# Ethernet.net
KiCad netlist of a schematic drawn in Altium Designer
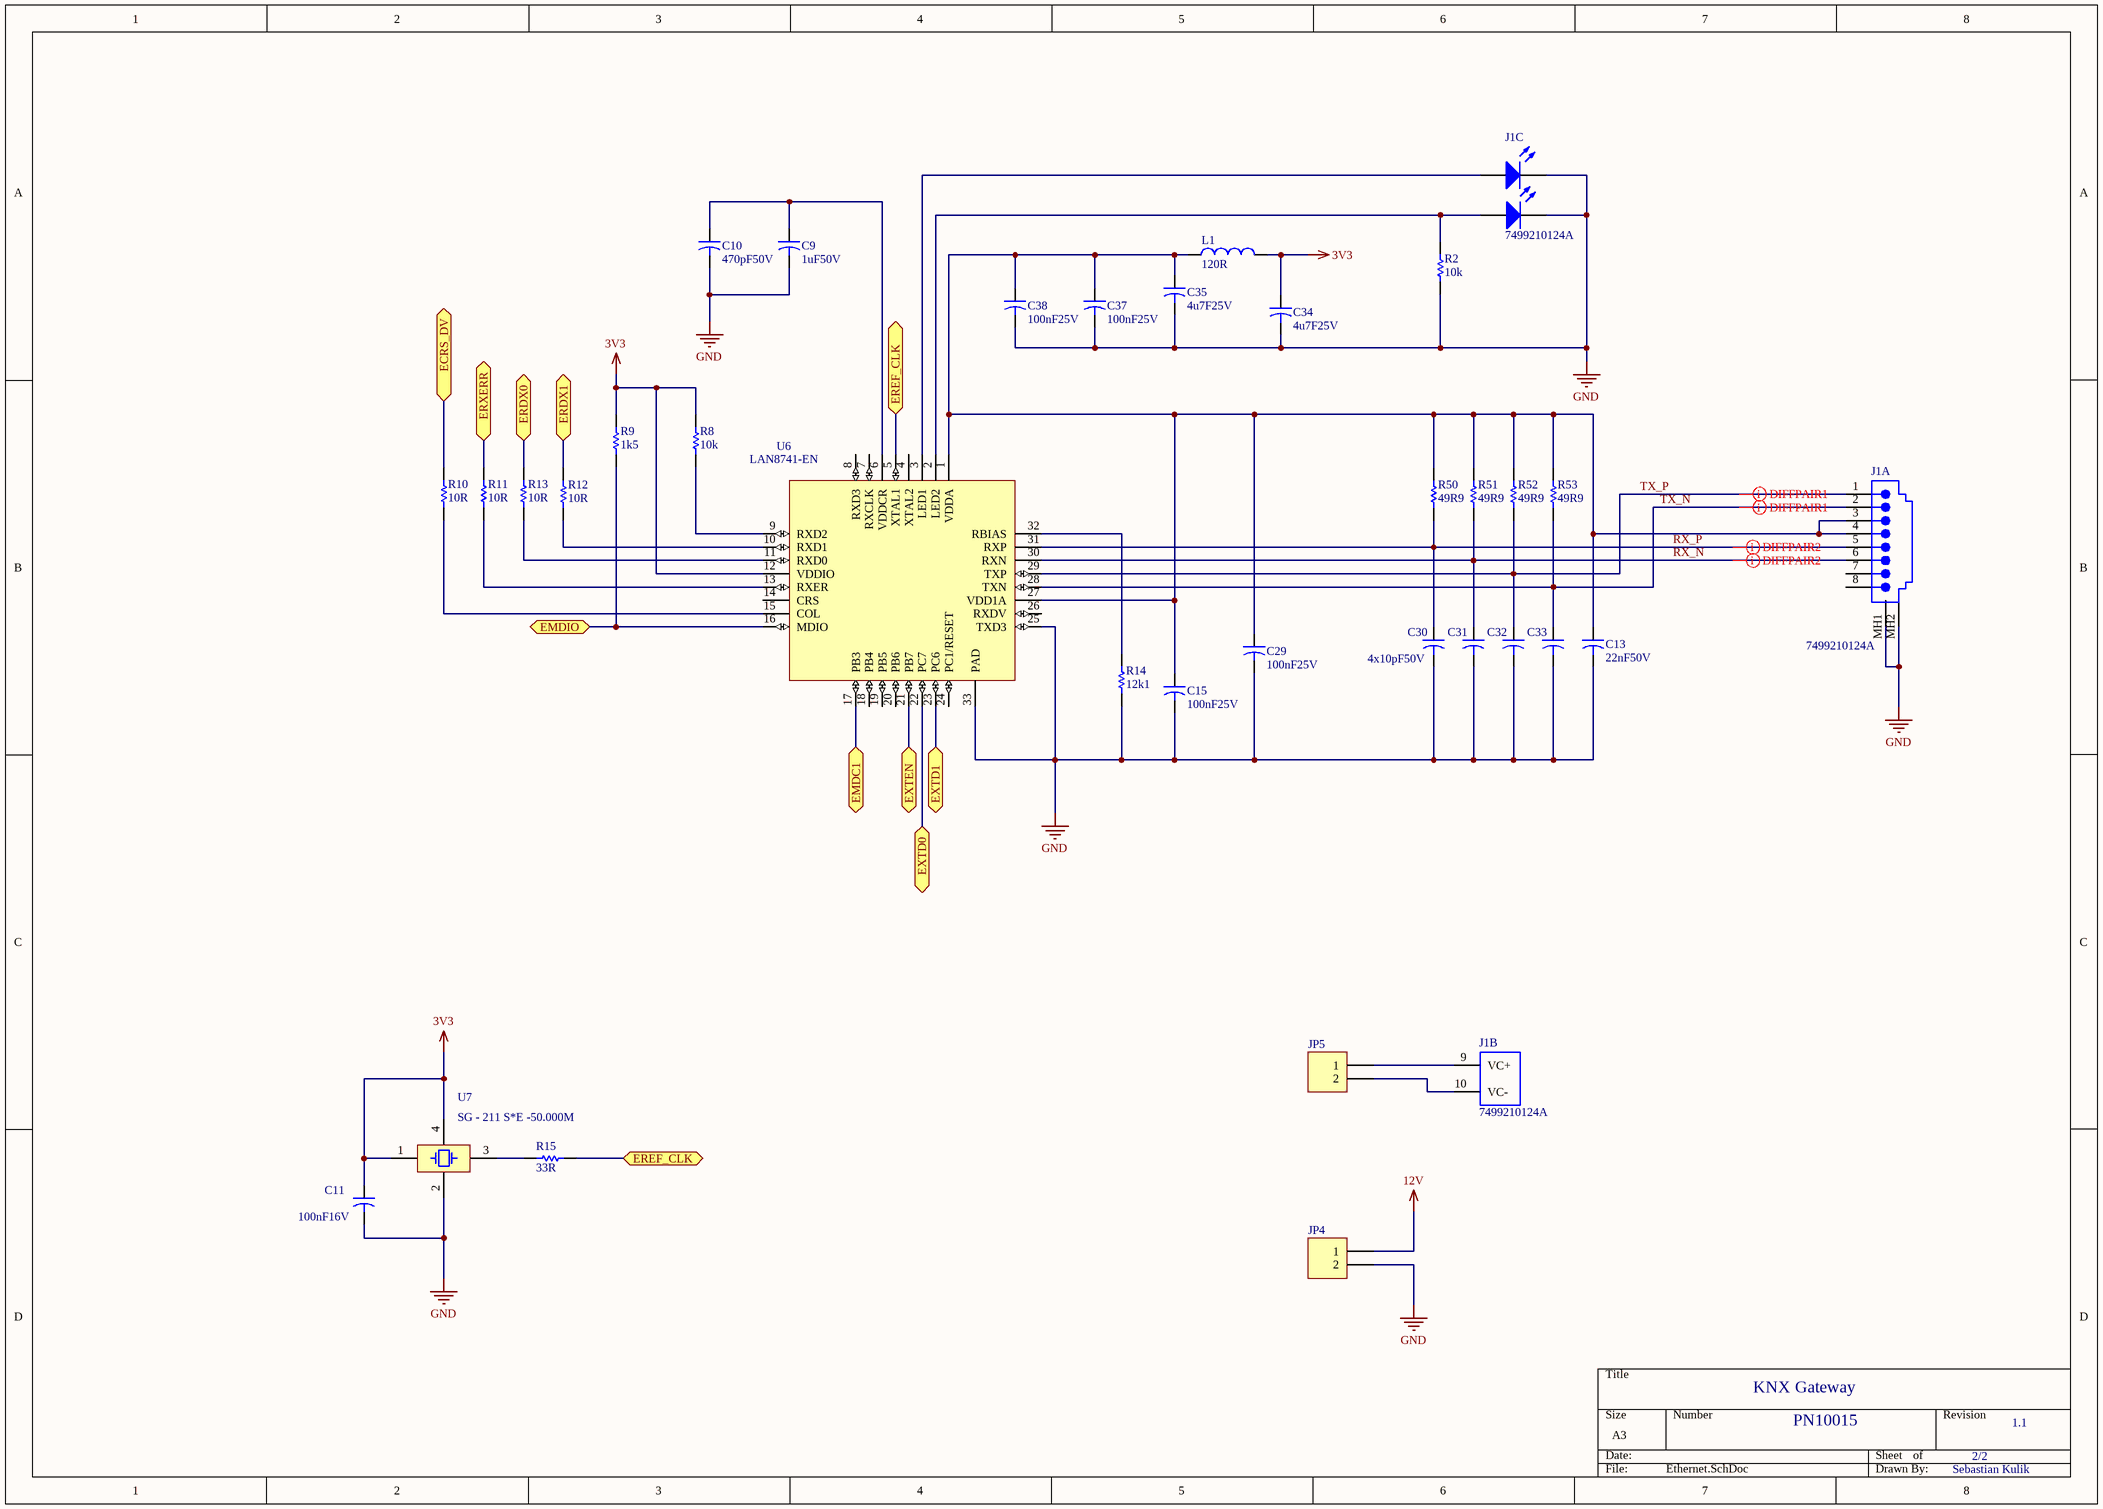
[diagram p0: Ethernet.SchDoc]

(export (version "E")
  (design (tool "Eeschema 10.0.6"))
  (components
    (comp (ref "C9")
      (value "1uF50V")
      (footprint "C0603")
      (description "C series, X5R, 10%")
      (fields
        (field (name "MANUFACTURER") "TDK")
        (field (name "Comment") "1uF50V_0603")
        (field (name "PUBLISHER") "Sebastian Kulik")
      )
      (libsource (lib "Capacitors") (part "1uF50V_0603"))
    )
    (comp (ref "C10")
      (value "470pF50V")
      (footprint "C0402")
      (description "AVX, 50V")
      (fields
        (field (name "MANUFACTURER") "AVX")
        (field (name "Comment") "470pF50V_0402")
        (field (name "PUBLISHER") "Sebastian Kulik")
      )
      (libsource (lib "Capacitors") (part "470pF50V_0402"))
    )
    (comp (ref "C11")
      (value "100nF16V")
      (footprint "C0402")
      (description "Capacitor")
      (fields
        (field (name "MANUFACTURER") "TDK")
        (field (name "Comment") "100nF16V_0402")
        (field (name "PUBLISHER") "Sebastian Kulik")
      )
      (libsource (lib "Capacitors") (part "100nF16V_0402"))
    )
    (comp (ref "C13")
      (value "22nF50V")
      (footprint "C0603")
      (description "AVX ,  X7R, 5%, 50V")
      (fields
        (field (name "MANUFACTURER") "AVX")
        (field (name "Comment") "22nF50V_0603")
        (field (name "PUBLISHER") "Sebastian Kulik")
      )
      (libsource (lib "Capacitors") (part "22nF50V_0603"))
    )
    (comp (ref "C15")
      (value "100nF25V")
      (footprint "C0402")
      (description "AVX, X5R, 10%, 25V")
      (fields
        (field (name "MANUFACTURER") "AVX")
        (field (name "Comment") "100nF25V_0402")
        (field (name "PUBLISHER") "Sebastian Kulik")
      )
      (libsource (lib "Capacitors") (part "100nF25V_0402"))
    )
    (comp (ref "C29")
      (value "100nF25V")
      (footprint "C0402")
      (description "AVX, X5R, 10%, 25V")
      (fields
        (field (name "MANUFACTURER") "AVX")
        (field (name "Comment") "100nF25V_0402")
        (field (name "PUBLISHER") "Sebastian Kulik")
      )
      (libsource (lib "Capacitors") (part "100nF25V_0402"))
    )
    (comp (ref "C30")
      (value "10pF50V_0603")
      (footprint "C0603")
      (description "AVX ,  +-0.5pF, 50V")
      (fields (field (name "MANUFACTURER") "AVX") (field (name "PUBLISHER") "Sebastian Kulik"))
      (libsource (lib "Capacitors") (part "10pF50V_0603"))
    )
    (comp (ref "C31")
      (value "10pF50V_0603")
      (footprint "C0603")
      (description "AVX ,  +-0.5pF, 50V")
      (fields (field (name "MANUFACTURER") "AVX") (field (name "PUBLISHER") "Sebastian Kulik"))
      (libsource (lib "Capacitors") (part "10pF50V_0603"))
    )
    (comp (ref "C32")
      (value "10pF50V_0603")
      (footprint "C0603")
      (description "AVX ,  +-0.5pF, 50V")
      (fields (field (name "MANUFACTURER") "AVX") (field (name "PUBLISHER") "Sebastian Kulik"))
      (libsource (lib "Capacitors") (part "10pF50V_0603"))
    )
    (comp (ref "C33")
      (value "10pF50V_0603")
      (footprint "C0603")
      (description "AVX ,  +-0.5pF, 50V")
      (fields (field (name "MANUFACTURER") "AVX") (field (name "PUBLISHER") "Sebastian Kulik"))
      (libsource (lib "Capacitors") (part "10pF50V_0603"))
    )
    (comp (ref "C34")
      (value "4u7F25V")
      (footprint "C0805")
      (description "TDK  C series, X7R, 10%, 25V")
      (fields
        (field (name "MANUFACTURER") "TDK")
        (field (name "Comment") "4u7F25V_0805")
        (field (name "PUBLISHER") "Sebastian Kulik")
      )
      (libsource (lib "Capacitors") (part "4u7F25V_0805"))
    )
    (comp (ref "C35")
      (value "4u7F25V")
      (footprint "C0805")
      (description "TDK  C series, X7R, 10%, 25V")
      (fields
        (field (name "MANUFACTURER") "TDK")
        (field (name "Comment") "4u7F25V_0805")
        (field (name "PUBLISHER") "Sebastian Kulik")
      )
      (libsource (lib "Capacitors") (part "4u7F25V_0805"))
    )
    (comp (ref "C37")
      (value "100nF25V")
      (footprint "C0402")
      (description "AVX, X5R, 10%, 25V")
      (fields
        (field (name "MANUFACTURER") "AVX")
        (field (name "Comment") "100nF25V_0402")
        (field (name "PUBLISHER") "Sebastian Kulik")
      )
      (libsource (lib "Capacitors") (part "100nF25V_0402"))
    )
    (comp (ref "C38")
      (value "100nF25V")
      (footprint "C0402")
      (description "AVX, X5R, 10%, 25V")
      (fields
        (field (name "MANUFACTURER") "AVX")
        (field (name "Comment") "100nF25V_0402")
        (field (name "PUBLISHER") "Sebastian Kulik")
      )
      (libsource (lib "Capacitors") (part "100nF25V_0402"))
    )
    (comp (ref "J1")
      (value "7499210124A")
      (footprint "7499210124A")
      (description "Modular Jack , Right Angle RJ-45, Low Profile")
      (fields (field (name "MANUFACTURER") "Wuerth Elektronik") (field (name "PUBLISHER") "Sebastian Kulik"))
      (libsource (lib "Connectors") (part "Ethernet, POE, WE7499210124A"))
    )
    (comp (ref "JP4")
      (value "Header-2")
      (footprint "HDR1X2")
      (description "Header, 5-Pin")
      (fields (field (name "PUBLISHER") "Sebastian Kulik"))
      (libsource (lib "Connectors") (part "Header-2"))
    )
    (comp (ref "JP5")
      (value "Header-2")
      (footprint "HDR1X2")
      (description "Header, 5-Pin")
      (fields (field (name "PUBLISHER") "Sebastian Kulik"))
      (libsource (lib "Connectors") (part "Header-2"))
    )
    (comp (ref "L1")
      (value "120R")
      (footprint "L0603")
      (description "Murata, Ferrit, 120Rx2A")
      (fields
        (field (name "MANUFACTURER") "Murata")
        (field (name "Comment") "120R4A_0603")
        (field (name "PUBLISHER") "Sebastian Kulik")
      )
      (libsource (lib "Passives") (part "120R4A_0603"))
    )
    (comp (ref "R2")
      (value "10k")
      (footprint "R0402")
      (description "Vishay CRCW series, 125mW, 1%")
      (fields
        (field (name "MANUFACTURER") "Vishay")
        (field (name "Comment") "10k_0402")
        (field (name "PUBLISHER") "Sebastian Kulik")
      )
      (libsource (lib "Resistors") (part "10k_0402"))
    )
    (comp (ref "R8")
      (value "10k")
      (footprint "R0402")
      (description "Vishay CRCW series, 125mW, 1%")
      (fields
        (field (name "MANUFACTURER") "Vishay")
        (field (name "Comment") "10k_0402")
        (field (name "PUBLISHER") "Sebastian Kulik")
      )
      (libsource (lib "Resistors") (part "10k_0402"))
    )
    (comp (ref "R9")
      (value "1k5")
      (footprint "R0402")
      (description "Vishay CRCW series, 125mW, 1%")
      (fields
        (field (name "MANUFACTURER") "Vishay")
        (field (name "Comment") "1k5_0402")
        (field (name "PUBLISHER") "Sebastian Kulik")
      )
      (libsource (lib "Resistors") (part "1k5_0402"))
    )
    (comp (ref "R10")
      (value "10R")
      (footprint "R0402")
      (description "Vishay CRCW series, 125mW, 1%")
      (fields
        (field (name "MANUFACTURER") "Vishay")
        (field (name "Comment") "10R_0402")
        (field (name "PUBLISHER") "Sebastian Kulik")
      )
      (libsource (lib "Resistors") (part "10R_0402"))
    )
    (comp (ref "R11")
      (value "10R")
      (footprint "R0402")
      (description "Vishay CRCW series, 125mW, 1%")
      (fields
        (field (name "MANUFACTURER") "Vishay")
        (field (name "Comment") "10R_0402")
        (field (name "PUBLISHER") "Sebastian Kulik")
      )
      (libsource (lib "Resistors") (part "10R_0402"))
    )
    (comp (ref "R12")
      (value "10R")
      (footprint "R0402")
      (description "Vishay CRCW series, 125mW, 1%")
      (fields
        (field (name "MANUFACTURER") "Vishay")
        (field (name "Comment") "10R_0402")
        (field (name "PUBLISHER") "Sebastian Kulik")
      )
      (libsource (lib "Resistors") (part "10R_0402"))
    )
    (comp (ref "R13")
      (value "10R")
      (footprint "R0402")
      (description "Vishay CRCW series, 125mW, 1%")
      (fields
        (field (name "MANUFACTURER") "Vishay")
        (field (name "Comment") "10R_0402")
        (field (name "PUBLISHER") "Sebastian Kulik")
      )
      (libsource (lib "Resistors") (part "10R_0402"))
    )
    (comp (ref "R14")
      (value "12k1")
      (footprint "R0603(1608)")
      (description "Vishay, CRCW series, 100mW, 1%")
      (fields
        (field (name "MANUFACTURER") "Vishay")
        (field (name "Comment") "12k1_0603")
        (field (name "PUBLISHER") "Sebastian Kulik")
      )
      (libsource (lib "Resistors") (part "12k1_0603"))
    )
    (comp (ref "R15")
      (value "33R")
      (footprint "R0402")
      (description "Vishay CRCW series, 63mW, 1%")
      (fields
        (field (name "MANUFACTURER") "Vishay")
        (field (name "Comment") "33R_0402")
        (field (name "PUBLISHER") "Sebastian Kulik")
      )
      (libsource (lib "Resistors") (part "33R_0402"))
    )
    (comp (ref "R50")
      (value "49R9")
      (footprint "R0402")
      (description "Vishay CRCW series, 63mW, 1%")
      (fields
        (field (name "MANUFACTURER") "Vishay")
        (field (name "Comment") "49R9_0402")
        (field (name "PUBLISHER") "Sebastian Kulik")
      )
      (libsource (lib "Resistors") (part "49R9_0402"))
    )
    (comp (ref "R51")
      (value "49R9")
      (footprint "R0402")
      (description "Vishay CRCW series, 63mW, 1%")
      (fields
        (field (name "MANUFACTURER") "Vishay")
        (field (name "Comment") "49R9_0402")
        (field (name "PUBLISHER") "Sebastian Kulik")
      )
      (libsource (lib "Resistors") (part "49R9_0402"))
    )
    (comp (ref "R52")
      (value "49R9")
      (footprint "R0402")
      (description "Vishay CRCW series, 63mW, 1%")
      (fields
        (field (name "MANUFACTURER") "Vishay")
        (field (name "Comment") "49R9_0402")
        (field (name "PUBLISHER") "Sebastian Kulik")
      )
      (libsource (lib "Resistors") (part "49R9_0402"))
    )
    (comp (ref "R53")
      (value "49R9")
      (footprint "R0402")
      (description "Vishay CRCW series, 63mW, 1%")
      (fields
        (field (name "MANUFACTURER") "Vishay")
        (field (name "Comment") "49R9_0402")
        (field (name "PUBLISHER") "Sebastian Kulik")
      )
      (libsource (lib "Resistors") (part "49R9_0402"))
    )
    (comp (ref "U6")
      (value "LAN8741-EN")
      (footprint "32M1-A_M")
      (description "Ethernet Phy")
      (fields (field (name "MANUFACTURER") "Microchip") (field (name "PUBLISHER") "Sebastian Kulik"))
      (libsource (lib "ICs") (part "LAN8741-EN"))
    )
    (comp (ref "U7")
      (value "SG - 211 S*E -50.000M")
      (footprint "SG - 211 S*E")
      (description "Crystal")
      (fields (field (name "MANUFACTURER") "Epson") (field (name "PUBLISHER") "Sebastian Kulik"))
      (libsource (lib "ICs") (part "SG - 211 S*E -50.000M"))
    )
  )
  (nets
    (net (code "1") (name "/ECRS_DV") (class "Default")
      (node (ref "R10") (pin "2") (pinfunction "2_2") (pintype "passive"))
    )
    (net (code "2") (name "/EMDC1") (class "Default")
      (node (ref "U6") (pin "17") (pinfunction "PB3_17") (pintype "bidirectional"))
    )
    (net (code "3") (name "/EMDIO") (class "Default")
      (node (ref "R9") (pin "1") (pinfunction "1_1") (pintype "passive"))
      (node (ref "U6") (pin "16") (pinfunction "MDIO_16") (pintype "bidirectional"))
    )
    (net (code "4") (name "/ERDX0") (class "Default")
      (node (ref "R13") (pin "2") (pinfunction "2_2") (pintype "passive"))
    )
    (net (code "5") (name "/ERDX1") (class "Default")
      (node (ref "R12") (pin "1") (pinfunction "1_1") (pintype "passive"))
    )
    (net (code "6") (name "/EREF_CLK") (class "Default")
      (node (ref "R15") (pin "2") (pinfunction "2_2") (pintype "passive"))
      (node (ref "U6") (pin "5") (pinfunction "XTAL1_5") (pintype "bidirectional"))
    )
    (net (code "7") (name "/ERXERR") (class "Default")
      (node (ref "R11") (pin "2") (pinfunction "2_2") (pintype "passive"))
    )
    (net (code "8") (name "/EXTD0") (class "Default")
      (node (ref "U6") (pin "22") (pinfunction "PC7_22") (pintype "bidirectional"))
    )
    (net (code "9") (name "/EXTD1") (class "Default")
      (node (ref "U6") (pin "23") (pinfunction "PC6_23") (pintype "bidirectional"))
    )
    (net (code "10") (name "/EXTEN") (class "Default")
      (node (ref "U6") (pin "21") (pinfunction "PB7_21") (pintype "bidirectional"))
    )
    (net (code "11") (name "/RX_N") (class "Default")
      (node (ref "C31") (pin "1") (pinfunction "1_1") (pintype "passive"))
      (node (ref "J1") (pin "6") (pinfunction "6_6") (pintype "passive"))
      (node (ref "R51") (pin "1") (pinfunction "1_1") (pintype "passive"))
      (node (ref "U6") (pin "30") (pinfunction "RXN_30") (pintype "passive"))
    )
    (net (code "12") (name "/RX_P") (class "Default")
      (node (ref "C30") (pin "1") (pinfunction "1_1") (pintype "passive"))
      (node (ref "J1") (pin "5") (pinfunction "5_5") (pintype "passive"))
      (node (ref "R50") (pin "1") (pinfunction "1_1") (pintype "passive"))
      (node (ref "U6") (pin "31") (pinfunction "RXP_31") (pintype "passive"))
    )
    (net (code "13") (name "/TX_N") (class "Default")
      (node (ref "C33") (pin "1") (pinfunction "1_1") (pintype "passive"))
      (node (ref "J1") (pin "2") (pinfunction "2_2") (pintype "passive"))
      (node (ref "R53") (pin "1") (pinfunction "1_1") (pintype "passive"))
      (node (ref "U6") (pin "28") (pinfunction "TXN_28") (pintype "bidirectional"))
    )
    (net (code "14") (name "/TX_P") (class "Default")
      (node (ref "C32") (pin "1") (pinfunction "1_1") (pintype "passive"))
      (node (ref "J1") (pin "1") (pinfunction "1_1") (pintype "passive"))
      (node (ref "R52") (pin "1") (pinfunction "1_1") (pintype "passive"))
      (node (ref "U6") (pin "29") (pinfunction "TXP_29") (pintype "bidirectional"))
    )
    (net (code "15") (name "3V3") (class "Default")
      (node (ref "C11") (pin "1") (pinfunction "1_1") (pintype "passive"))
      (node (ref "C34") (pin "1") (pinfunction "1_1") (pintype "passive"))
      (node (ref "L1") (pin "2") (pinfunction "2_2") (pintype "passive"))
      (node (ref "R8") (pin "2") (pinfunction "2_2") (pintype "passive"))
      (node (ref "R9") (pin "2") (pinfunction "2_2") (pintype "passive"))
      (node (ref "U6") (pin "12") (pinfunction "VDDIO_12") (pintype "passive"))
      (node (ref "U7") (pin "1") (pinfunction "E/D_1") (pintype "passive"))
      (node (ref "U7") (pin "4") (pinfunction "VCC_4") (pintype "passive"))
    )
    (net (code "16") (name "12V") (class "Default")
      (node (ref "JP4") (pin "1") (pinfunction "1_1") (pintype "passive"))
    )
    (net (code "17") (name "GND") (class "Default")
      (node (ref "C10") (pin "2") (pinfunction "2_2") (pintype "passive"))
      (node (ref "C11") (pin "2") (pinfunction "2_2") (pintype "passive"))
      (node (ref "C13") (pin "2") (pinfunction "2_2") (pintype "passive"))
      (node (ref "C15") (pin "2") (pinfunction "2_2") (pintype "passive"))
      (node (ref "C29") (pin "2") (pinfunction "2_2") (pintype "passive"))
      (node (ref "C30") (pin "2") (pinfunction "2_2") (pintype "passive"))
      (node (ref "C31") (pin "2") (pinfunction "2_2") (pintype "passive"))
      (node (ref "C32") (pin "2") (pinfunction "2_2") (pintype "passive"))
      (node (ref "C33") (pin "2") (pinfunction "2_2") (pintype "passive"))
      (node (ref "C34") (pin "2") (pinfunction "2_2") (pintype "passive"))
      (node (ref "C35") (pin "2") (pinfunction "2_2") (pintype "passive"))
      (node (ref "C37") (pin "2") (pinfunction "2_2") (pintype "passive"))
      (node (ref "C38") (pin "2") (pinfunction "2_2") (pintype "passive"))
      (node (ref "C9") (pin "2") (pinfunction "2_2") (pintype "passive"))
      (node (ref "J1") (pin "11") (pinfunction "K_11") (pintype "passive"))
      (node (ref "J1") (pin "13") (pinfunction "K_13") (pintype "passive"))
      (node (ref "J1") (pin "MH1") (pinfunction "Shield_MH1") (pintype "passive"))
      (node (ref "J1") (pin "MH2") (pinfunction "Shield_MH2") (pintype "passive"))
      (node (ref "JP4") (pin "2") (pinfunction "2_2") (pintype "passive"))
      (node (ref "R14") (pin "1") (pinfunction "1_1") (pintype "passive"))
      (node (ref "R2") (pin "1") (pinfunction "1_1") (pintype "passive"))
      (node (ref "U6") (pin "25") (pinfunction "TXD3_25") (pintype "bidirectional"))
      (node (ref "U6") (pin "33") (pinfunction "PAD_33") (pintype "power_in"))
      (node (ref "U7") (pin "2") (pinfunction "GND_2") (pintype "passive"))
    )
    (net (code "18") (name "Net-(J1B-VC+)") (class "Default")
      (node (ref "J1") (pin "9") (pinfunction "VC+_9") (pintype "passive"))
      (node (ref "JP5") (pin "1") (pinfunction "1_1") (pintype "passive"))
    )
    (net (code "19") (name "Net-(J1B-VC-)") (class "Default")
      (node (ref "J1") (pin "10") (pinfunction "VC-_10") (pintype "passive"))
      (node (ref "JP5") (pin "2") (pinfunction "2_2") (pintype "passive"))
    )
    (net (code "20") (name "Net-(U6-COL)") (class "Default")
      (node (ref "R10") (pin "1") (pinfunction "1_1") (pintype "passive"))
      (node (ref "U6") (pin "15") (pinfunction "COL_15") (pintype "passive"))
    )
    (net (code "21") (name "Net-(U6-LED1)") (class "Default")
      (node (ref "J1") (pin "12") (pinfunction "A_12") (pintype "passive"))
      (node (ref "U6") (pin "3") (pinfunction "LED1_3") (pintype "power_in"))
    )
    (net (code "22") (name "Net-(U6-LED2)") (class "Default")
      (node (ref "J1") (pin "14") (pinfunction "A_14") (pintype "passive"))
      (node (ref "R2") (pin "2") (pinfunction "2_2") (pintype "passive"))
      (node (ref "U6") (pin "2") (pinfunction "LED2_2") (pintype "passive"))
    )
    (net (code "23") (name "Net-(U6-RBIAS)") (class "Default")
      (node (ref "R14") (pin "2") (pinfunction "2_2") (pintype "passive"))
      (node (ref "U6") (pin "32") (pinfunction "RBIAS_32") (pintype "power_in"))
    )
    (net (code "24") (name "Net-(U6-RXD0)") (class "Default")
      (node (ref "R13") (pin "1") (pinfunction "1_1") (pintype "passive"))
      (node (ref "U6") (pin "11") (pinfunction "RXD0_11") (pintype "bidirectional"))
    )
    (net (code "25") (name "Net-(U6-RXD1)") (class "Default")
      (node (ref "R12") (pin "2") (pinfunction "2_2") (pintype "passive"))
      (node (ref "U6") (pin "10") (pinfunction "RXD1_10") (pintype "bidirectional"))
    )
    (net (code "26") (name "Net-(U6-RXD2)") (class "Default")
      (node (ref "R8") (pin "1") (pinfunction "1_1") (pintype "passive"))
      (node (ref "U6") (pin "9") (pinfunction "RXD2_9") (pintype "bidirectional"))
    )
    (net (code "27") (name "Net-(U6-RXER)") (class "Default")
      (node (ref "R11") (pin "1") (pinfunction "1_1") (pintype "passive"))
      (node (ref "U6") (pin "13") (pinfunction "RXER_13") (pintype "bidirectional"))
    )
    (net (code "28") (name "Net-(U6-VDD1A)") (class "Default")
      (node (ref "C13") (pin "1") (pinfunction "1_1") (pintype "passive"))
      (node (ref "C15") (pin "1") (pinfunction "1_1") (pintype "passive"))
      (node (ref "C29") (pin "1") (pinfunction "1_1") (pintype "passive"))
      (node (ref "C35") (pin "1") (pinfunction "1_1") (pintype "passive"))
      (node (ref "C37") (pin "1") (pinfunction "1_1") (pintype "passive"))
      (node (ref "C38") (pin "1") (pinfunction "1_1") (pintype "passive"))
      (node (ref "J1") (pin "3") (pinfunction "3_3") (pintype "passive"))
      (node (ref "J1") (pin "4") (pinfunction "4_4") (pintype "passive"))
      (node (ref "L1") (pin "1") (pinfunction "1_1") (pintype "passive"))
      (node (ref "R50") (pin "2") (pinfunction "2_2") (pintype "passive"))
      (node (ref "R51") (pin "2") (pinfunction "2_2") (pintype "passive"))
      (node (ref "R52") (pin "2") (pinfunction "2_2") (pintype "passive"))
      (node (ref "R53") (pin "2") (pinfunction "2_2") (pintype "passive"))
      (node (ref "U6") (pin "1") (pinfunction "VDDA_1") (pintype "passive"))
      (node (ref "U6") (pin "27") (pinfunction "VDD1A_27") (pintype "passive"))
    )
    (net (code "29") (name "Net-(U6-VDDCR)") (class "Default")
      (node (ref "C10") (pin "1") (pinfunction "1_1") (pintype "passive"))
      (node (ref "C9") (pin "1") (pinfunction "1_1") (pintype "passive"))
      (node (ref "U6") (pin "6") (pinfunction "VDDCR_6") (pintype "passive"))
    )
    (net (code "30") (name "Net-(U7-OSC2)") (class "Default")
      (node (ref "R15") (pin "1") (pinfunction "1_1") (pintype "passive"))
      (node (ref "U7") (pin "3") (pinfunction "OSC2_3") (pintype "passive"))
    )
    (net (code "31") (name "unconnected-(J1-Pad7)") (class "Default")
      (node (ref "J1") (pin "7") (pinfunction "7_7") (pintype "passive"))
    )
    (net (code "32") (name "unconnected-(J1-Pad8)") (class "Default")
      (node (ref "J1") (pin "8") (pinfunction "8_8") (pintype "passive"))
    )
    (net (code "33") (name "unconnected-(U6-CRS-Pad14)") (class "Default")
      (node (ref "U6") (pin "14") (pinfunction "CRS_14") (pintype "passive"))
    )
    (net (code "34") (name "unconnected-(U6-PB4-Pad18)") (class "Default")
      (node (ref "U6") (pin "18") (pinfunction "PB4_18") (pintype "bidirectional"))
    )
    (net (code "35") (name "unconnected-(U6-PB5-Pad19)") (class "Default")
      (node (ref "U6") (pin "19") (pinfunction "PB5_19") (pintype "bidirectional"))
    )
    (net (code "36") (name "unconnected-(U6-PB6-Pad20)") (class "Default")
      (node (ref "U6") (pin "20") (pinfunction "PB6_20") (pintype "bidirectional"))
    )
    (net (code "37") (name "unconnected-(U6-PC1{slash}RESET-Pad24)") (class "Default")
      (node (ref "U6") (pin "24") (pinfunction "PC1/RESET_24") (pintype "bidirectional"))
    )
    (net (code "38") (name "unconnected-(U6-RXCLK-Pad7)") (class "Default")
      (node (ref "U6") (pin "7") (pinfunction "RXCLK_7") (pintype "bidirectional"))
    )
    (net (code "39") (name "unconnected-(U6-RXD3-Pad8)") (class "Default")
      (node (ref "U6") (pin "8") (pinfunction "RXD3_8") (pintype "bidirectional"))
    )
    (net (code "40") (name "unconnected-(U6-RXDV-Pad26)") (class "Default")
      (node (ref "U6") (pin "26") (pinfunction "RXDV_26") (pintype "bidirectional"))
    )
    (net (code "41") (name "unconnected-(U6-XTAL2-Pad4)") (class "Default")
      (node (ref "U6") (pin "4") (pinfunction "XTAL2_4") (pintype "power_in"))
    )
  )
)
